# TopLevel.net
KiCad netlist of a schematic drawn in Altium Designer
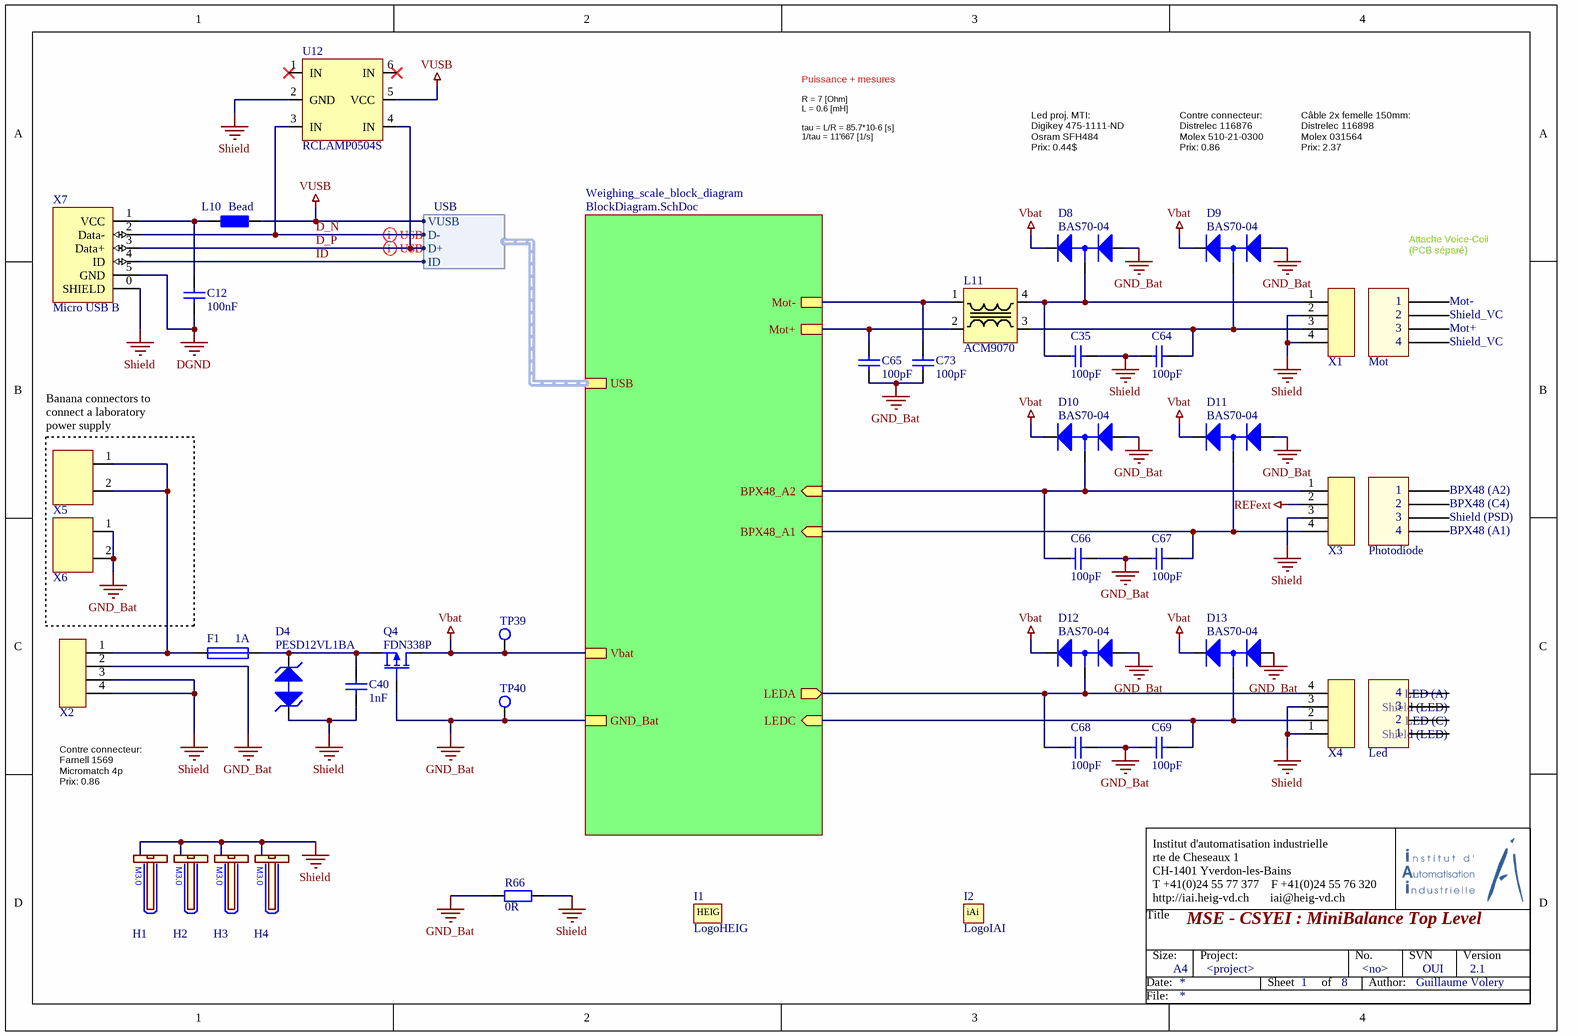
[diagram p0: TopLevel.SchDoc]

(export (version "E")
  (design (tool "Eeschema 10.0.6"))
  (components
    (comp (ref "C12")
      (value "100nF")
      (footprint "CAPC2012N")
      (description "Capacitor")
      (libsource (lib "Balance") (part "Cap_100nF"))
    )
    (comp (ref "C35")
      (value "100pF")
      (footprint "CAPC2012N")
      (description "Capacitor")
      (libsource (lib "Balance") (part "Cap_100pF"))
    )
    (comp (ref "C40")
      (value "1nF")
      (footprint "CAPC2012N")
      (description "Capacitor")
      (libsource (lib "Balance") (part "Cap_1nF"))
    )
    (comp (ref "C64")
      (value "100pF")
      (footprint "CAPC2012N")
      (description "Capacitor")
      (libsource (lib "Balance") (part "Cap_100pF"))
    )
    (comp (ref "C65")
      (value "100pF")
      (footprint "CAPC2012N")
      (description "Capacitor")
      (libsource (lib "Balance") (part "Cap_100pF"))
    )
    (comp (ref "C66")
      (value "100pF")
      (footprint "CAPC2012N")
      (description "Capacitor")
      (libsource (lib "Balance") (part "Cap_100pF"))
    )
    (comp (ref "C67")
      (value "100pF")
      (footprint "CAPC2012N")
      (description "Capacitor")
      (libsource (lib "Balance") (part "Cap_100pF"))
    )
    (comp (ref "C68")
      (value "100pF")
      (footprint "CAPC2012N")
      (description "Capacitor")
      (libsource (lib "Balance") (part "Cap_100pF"))
    )
    (comp (ref "C69")
      (value "100pF")
      (footprint "CAPC2012N")
      (description "Capacitor")
      (libsource (lib "Balance") (part "Cap_100pF"))
    )
    (comp (ref "C73")
      (value "100pF")
      (footprint "CAPC2012N")
      (description "Capacitor")
      (libsource (lib "Balance") (part "Cap_100pF"))
    )
    (comp (ref "D4")
      (value "PESD12VL1BA")
      (footprint "SOD323")
      (libsource (lib "Balance") (part "PESD12VL1BA"))
    )
    (comp (ref "D8") (value "BAS70-04") (footprint "SOT23-3N") (libsource (lib "Balance") (part "BAS70-04")))
    (comp (ref "D9") (value "BAS70-04") (footprint "SOT23-3N") (libsource (lib "Balance") (part "BAS70-04")))
    (comp (ref "D10") (value "BAS70-04") (footprint "SOT23-3N") (libsource (lib "Balance") (part "BAS70-04")))
    (comp (ref "D11") (value "BAS70-04") (footprint "SOT23-3N") (libsource (lib "Balance") (part "BAS70-04")))
    (comp (ref "D12") (value "BAS70-04") (footprint "SOT23-3N") (libsource (lib "Balance") (part "BAS70-04")))
    (comp (ref "D13") (value "BAS70-04") (footprint "SOT23-3N") (libsource (lib "Balance") (part "BAS70-04")))
    (comp (ref "F1")
      (value "1A")
      (footprint "RESC2012N")
      (description "MFU0805FF01000P100")
      (libsource (lib "Balance") (part "Fuse_1A"))
    )
    (comp (ref "H1") (value "Mhole M3") (footprint "MHOLE_M3.0") (libsource (lib "Balance") (part "M3")))
    (comp (ref "H2") (value "Mhole M3") (footprint "MHOLE_M3.0") (libsource (lib "Balance") (part "M3")))
    (comp (ref "H3") (value "Mhole M3") (footprint "MHOLE_M3.0") (libsource (lib "Balance") (part "M3")))
    (comp (ref "H4") (value "Mhole M3") (footprint "MHOLE_M3.0") (libsource (lib "Balance") (part "M3")))
    (comp (ref "I1")
      (value "LogoHEIG")
      (footprint "LOGO HEIG-VD_TOP/solder TOP")
      (libsource (lib "Balance") (part "LogoHEIG"))
    )
    (comp (ref "I2")
      (value "LogoIAI")
      (footprint "LOGO_IAI_TOP")
      (libsource (lib "Balance") (part "LogoIAI"))
    )
    (comp (ref "L10") (value "Bead") (footprint "RESC2012N") (libsource (lib "Balance") (part "Bead")))
    (comp (ref "L11") (value "ACM9070") (footprint "ACM9070") (libsource (lib "Balance") (part "ACM9070")))
    (comp (ref "Q4")
      (value "FDN338P")
      (footprint "SOT23-3N")
      (description "MOSFet P")
      (libsource (lib "Balance") (part "FDN338P"))
    )
    (comp (ref "R66")
      (value "0R")
      (footprint "RESC2012N")
      (description "Resistor")
      (libsource (lib "Balance") (part "Res_0R"))
    )
    (comp (ref "TP39")
      (value "TP")
      (footprint "Testpoint")
      (description "=Value")
      (libsource (lib "Balance") (part "TP"))
    )
    (comp (ref "TP40")
      (value "TP")
      (footprint "Testpoint")
      (description "=Value")
      (libsource (lib "Balance") (part "TP"))
    )
    (comp (ref "U12")
      (value "RCLAMP0504S")
      (footprint "SOT-23-6")
      (libsource (lib "Balance") (part "RCLAMP0504S.TCT"))
    )
    (comp (ref "X1")
      (value "MicroMatch4p")
      (footprint "MicroMatch4p")
      (libsource (lib "") (part "MicroMatch4p_1"))
    )
    (comp (ref "X2")
      (value "MicroMatch4p")
      (footprint "MicroMatch4p")
      (libsource (lib "") (part "MicroMatch4p_2"))
    )
    (comp (ref "X3")
      (value "MicroMatch4p")
      (footprint "MicroMatch4p")
      (libsource (lib "") (part "MicroMatch4p_1"))
    )
    (comp (ref "X4")
      (value "MicroMatch4p")
      (footprint "MicroMatch4p")
      (libsource (lib "Balance") (part "MicroMatch4p"))
    )
    (comp (ref "X5")
      (value "Fiche Banane Rouge 4mm")
      (footprint "BANANE")
      (libsource (lib "Balance") (part "Fiche Banane Rouge 4mm"))
    )
    (comp (ref "X6")
      (value "Fiche Banane Noire 4mm")
      (footprint "BANANE")
      (libsource (lib "Balance") (part "Fiche Banane Noire 4mm"))
    )
    (comp (ref "X7")
      (value "Micro USB B")
      (footprint "Micro_USB_ZX62-B-5PA(33)")
      (libsource (lib "Balance") (part "Micro_USB_ZX62-B-5PA(33)"))
    )
  )
  (nets
    (net (code "2") (name "/BPX48_A1") (class "Default")
      (node (ref "C67") (pin "2") (pinfunction "2_2") (pintype "passive"))
      (node (ref "D11") (pin "3") (pinfunction "A/K_3") (pintype "passive"))
      (node (ref "X3") (pin "4") (pintype "passive"))
    )
    (net (code "3") (name "/BPX48_A2") (class "Default")
      (node (ref "C66") (pin "1") (pinfunction "1_1") (pintype "passive"))
      (node (ref "D10") (pin "3") (pinfunction "A/K_3") (pintype "passive"))
      (node (ref "X3") (pin "1") (pintype "passive"))
    )
    (net (code "4") (name "/D_N") (class "Default")
      (node (ref "U12") (pin "3") (pinfunction "IN_3") (pintype "passive"))
      (node (ref "X7") (pin "2") (pinfunction "Data-_2") (pintype "bidirectional"))
    )
    (net (code "5") (name "/D_P") (class "Default")
      (node (ref "U12") (pin "4") (pinfunction "IN_4") (pintype "passive"))
      (node (ref "X7") (pin "3") (pinfunction "Data+_3") (pintype "bidirectional"))
    )
    (net (code "6") (name "/ID") (class "Default")
      (node (ref "X7") (pin "4") (pinfunction "ID_4") (pintype "bidirectional"))
    )
    (net (code "7") (name "/LEDA") (class "Default")
      (node (ref "C68") (pin "1") (pinfunction "1_1") (pintype "passive"))
      (node (ref "D12") (pin "3") (pinfunction "A/K_3") (pintype "passive"))
      (node (ref "X4") (pin "4") (pintype "passive"))
    )
    (net (code "8") (name "/LEDC") (class "Default")
      (node (ref "C69") (pin "2") (pinfunction "2_2") (pintype "passive"))
      (node (ref "D13") (pin "3") (pinfunction "A/K_3") (pintype "passive"))
      (node (ref "X4") (pin "2") (pintype "passive"))
    )
    (net (code "9") (name "/Mot+") (class "Default")
      (node (ref "C65") (pin "2") (pinfunction "2_2") (pintype "passive"))
      (node (ref "L11") (pin "2") (pintype "passive"))
    )
    (net (code "10") (name "/Mot-") (class "Default")
      (node (ref "C73") (pin "2") (pinfunction "2_2") (pintype "passive"))
      (node (ref "L11") (pin "1") (pintype "passive"))
    )
    (net (code "12") (name "DGND") (class "Default")
      (node (ref "C12") (pin "1") (pinfunction "1_1") (pintype "passive"))
      (node (ref "X7") (pin "5") (pinfunction "GND_5") (pintype "power_in"))
    )
    (net (code "13") (name "GND_Bat") (class "Default")
      (node (ref "C65") (pin "1") (pinfunction "1_1") (pintype "passive"))
      (node (ref "C66") (pin "2") (pinfunction "2_2") (pintype "passive"))
      (node (ref "C67") (pin "1") (pinfunction "1_1") (pintype "passive"))
      (node (ref "C68") (pin "2") (pinfunction "2_2") (pintype "passive"))
      (node (ref "C69") (pin "1") (pinfunction "1_1") (pintype "passive"))
      (node (ref "C73") (pin "1") (pinfunction "1_1") (pintype "passive"))
      (node (ref "D10") (pin "1") (pinfunction "A_1") (pintype "passive"))
      (node (ref "D11") (pin "1") (pinfunction "A_1") (pintype "passive"))
      (node (ref "D12") (pin "1") (pinfunction "A_1") (pintype "passive"))
      (node (ref "D13") (pin "1") (pinfunction "A_1") (pintype "passive"))
      (node (ref "D8") (pin "1") (pinfunction "A_1") (pintype "passive"))
      (node (ref "D9") (pin "1") (pinfunction "A_1") (pintype "passive"))
      (node (ref "Q4") (pin "1") (pinfunction "G_1") (pintype "passive"))
      (node (ref "R66") (pin "1") (pinfunction "1_1") (pintype "passive"))
      (node (ref "TP40") (pin "1") (pinfunction "1_1") (pintype "passive"))
      (node (ref "X2") (pin "2") (pintype "passive"))
      (node (ref "X6") (pin "1") (pintype "passive"))
      (node (ref "X6") (pin "2") (pintype "passive"))
    )
    (net (code "14") (name "Net-(D4-K2)") (class "Default")
      (node (ref "C40") (pin "2") (pinfunction "2_2") (pintype "passive"))
      (node (ref "D4") (pin "2") (pinfunction "K2_2") (pintype "passive"))
      (node (ref "F1") (pin "2") (pinfunction "2_2") (pintype "passive"))
      (node (ref "Q4") (pin "2") (pinfunction "S_2") (pintype "passive"))
    )
    (net (code "15") (name "Net-(D8-A{slash}K)") (class "Default")
      (node (ref "C35") (pin "1") (pinfunction "1_1") (pintype "passive"))
      (node (ref "D8") (pin "3") (pinfunction "A/K_3") (pintype "passive"))
      (node (ref "L11") (pin "4") (pintype "passive"))
      (node (ref "X1") (pin "1") (pintype "passive"))
    )
    (net (code "16") (name "Net-(D9-A{slash}K)") (class "Default")
      (node (ref "C64") (pin "2") (pinfunction "2_2") (pintype "passive"))
      (node (ref "D9") (pin "3") (pinfunction "A/K_3") (pintype "passive"))
      (node (ref "L11") (pin "3") (pintype "passive"))
      (node (ref "X1") (pin "3") (pintype "passive"))
    )
    (net (code "17") (name "Net-(F1-Pad1)") (class "Default")
      (node (ref "F1") (pin "1") (pinfunction "1_1") (pintype "passive"))
      (node (ref "X2") (pin "1") (pintype "passive"))
      (node (ref "X5") (pin "1") (pintype "passive"))
      (node (ref "X5") (pin "2") (pintype "passive"))
    )
    (net (code "18") (name "Net-(X7-VCC)") (class "Default")
      (node (ref "C12") (pin "2") (pinfunction "2_2") (pintype "passive"))
      (node (ref "L10") (pin "1") (pinfunction "1_1") (pintype "passive"))
      (node (ref "X7") (pin "1") (pinfunction "VCC_1") (pintype "power_in"))
    )
    (net (code "19") (name "REFext") (class "Default") (node (ref "X3") (pin "2") (pintype "passive")))
    (net (code "20") (name "Shield") (class "Default")
      (node (ref "C35") (pin "2") (pinfunction "2_2") (pintype "passive"))
      (node (ref "C40") (pin "1") (pinfunction "1_1") (pintype "passive"))
      (node (ref "C64") (pin "1") (pinfunction "1_1") (pintype "passive"))
      (node (ref "D4") (pin "1") (pinfunction "K1_1") (pintype "passive"))
      (node (ref "H1") (pin "1") (pinfunction "S_1") (pintype "passive"))
      (node (ref "H2") (pin "1") (pinfunction "S_1") (pintype "passive"))
      (node (ref "H3") (pin "1") (pinfunction "S_1") (pintype "passive"))
      (node (ref "H4") (pin "1") (pinfunction "S_1") (pintype "passive"))
      (node (ref "R66") (pin "2") (pinfunction "2_2") (pintype "passive"))
      (node (ref "U12") (pin "2") (pinfunction "GND_2") (pintype "passive"))
      (node (ref "X1") (pin "2") (pintype "passive"))
      (node (ref "X1") (pin "4") (pintype "passive"))
      (node (ref "X2") (pin "3") (pintype "passive"))
      (node (ref "X2") (pin "4") (pintype "passive"))
      (node (ref "X3") (pin "3") (pintype "passive"))
      (node (ref "X4") (pin "1") (pintype "passive"))
      (node (ref "X4") (pin "3") (pintype "passive"))
      (node (ref "X7") (pin "0") (pinfunction "SHIELD_0") (pintype "power_in"))
    )
    (net (code "21") (name "VUSB") (class "Default")
      (node (ref "L10") (pin "2") (pinfunction "2_2") (pintype "passive"))
      (node (ref "U12") (pin "5") (pinfunction "VCC_5") (pintype "power_in"))
    )
    (net (code "22") (name "Vbat") (class "Default")
      (node (ref "D10") (pin "2") (pinfunction "K_2") (pintype "passive"))
      (node (ref "D11") (pin "2") (pinfunction "K_2") (pintype "passive"))
      (node (ref "D12") (pin "2") (pinfunction "K_2") (pintype "passive"))
      (node (ref "D13") (pin "2") (pinfunction "K_2") (pintype "passive"))
      (node (ref "D8") (pin "2") (pinfunction "K_2") (pintype "passive"))
      (node (ref "D9") (pin "2") (pinfunction "K_2") (pintype "passive"))
      (node (ref "Q4") (pin "3") (pinfunction "D_3") (pintype "passive"))
      (node (ref "TP39") (pin "1") (pinfunction "1_1") (pintype "passive"))
    )
    (net (code "23") (name "unconnected-(U12-IN-Pad1)") (class "Default")
      (node (ref "U12") (pin "1") (pinfunction "IN_1") (pintype "passive+no_connect"))
    )
    (net (code "24") (name "unconnected-(U12-IN-Pad6)") (class "Default")
      (node (ref "U12") (pin "6") (pinfunction "IN_6") (pintype "passive+no_connect"))
    )
  )
)
